# M623E.net
KiCad netlist of a schematic drawn in EAGLE
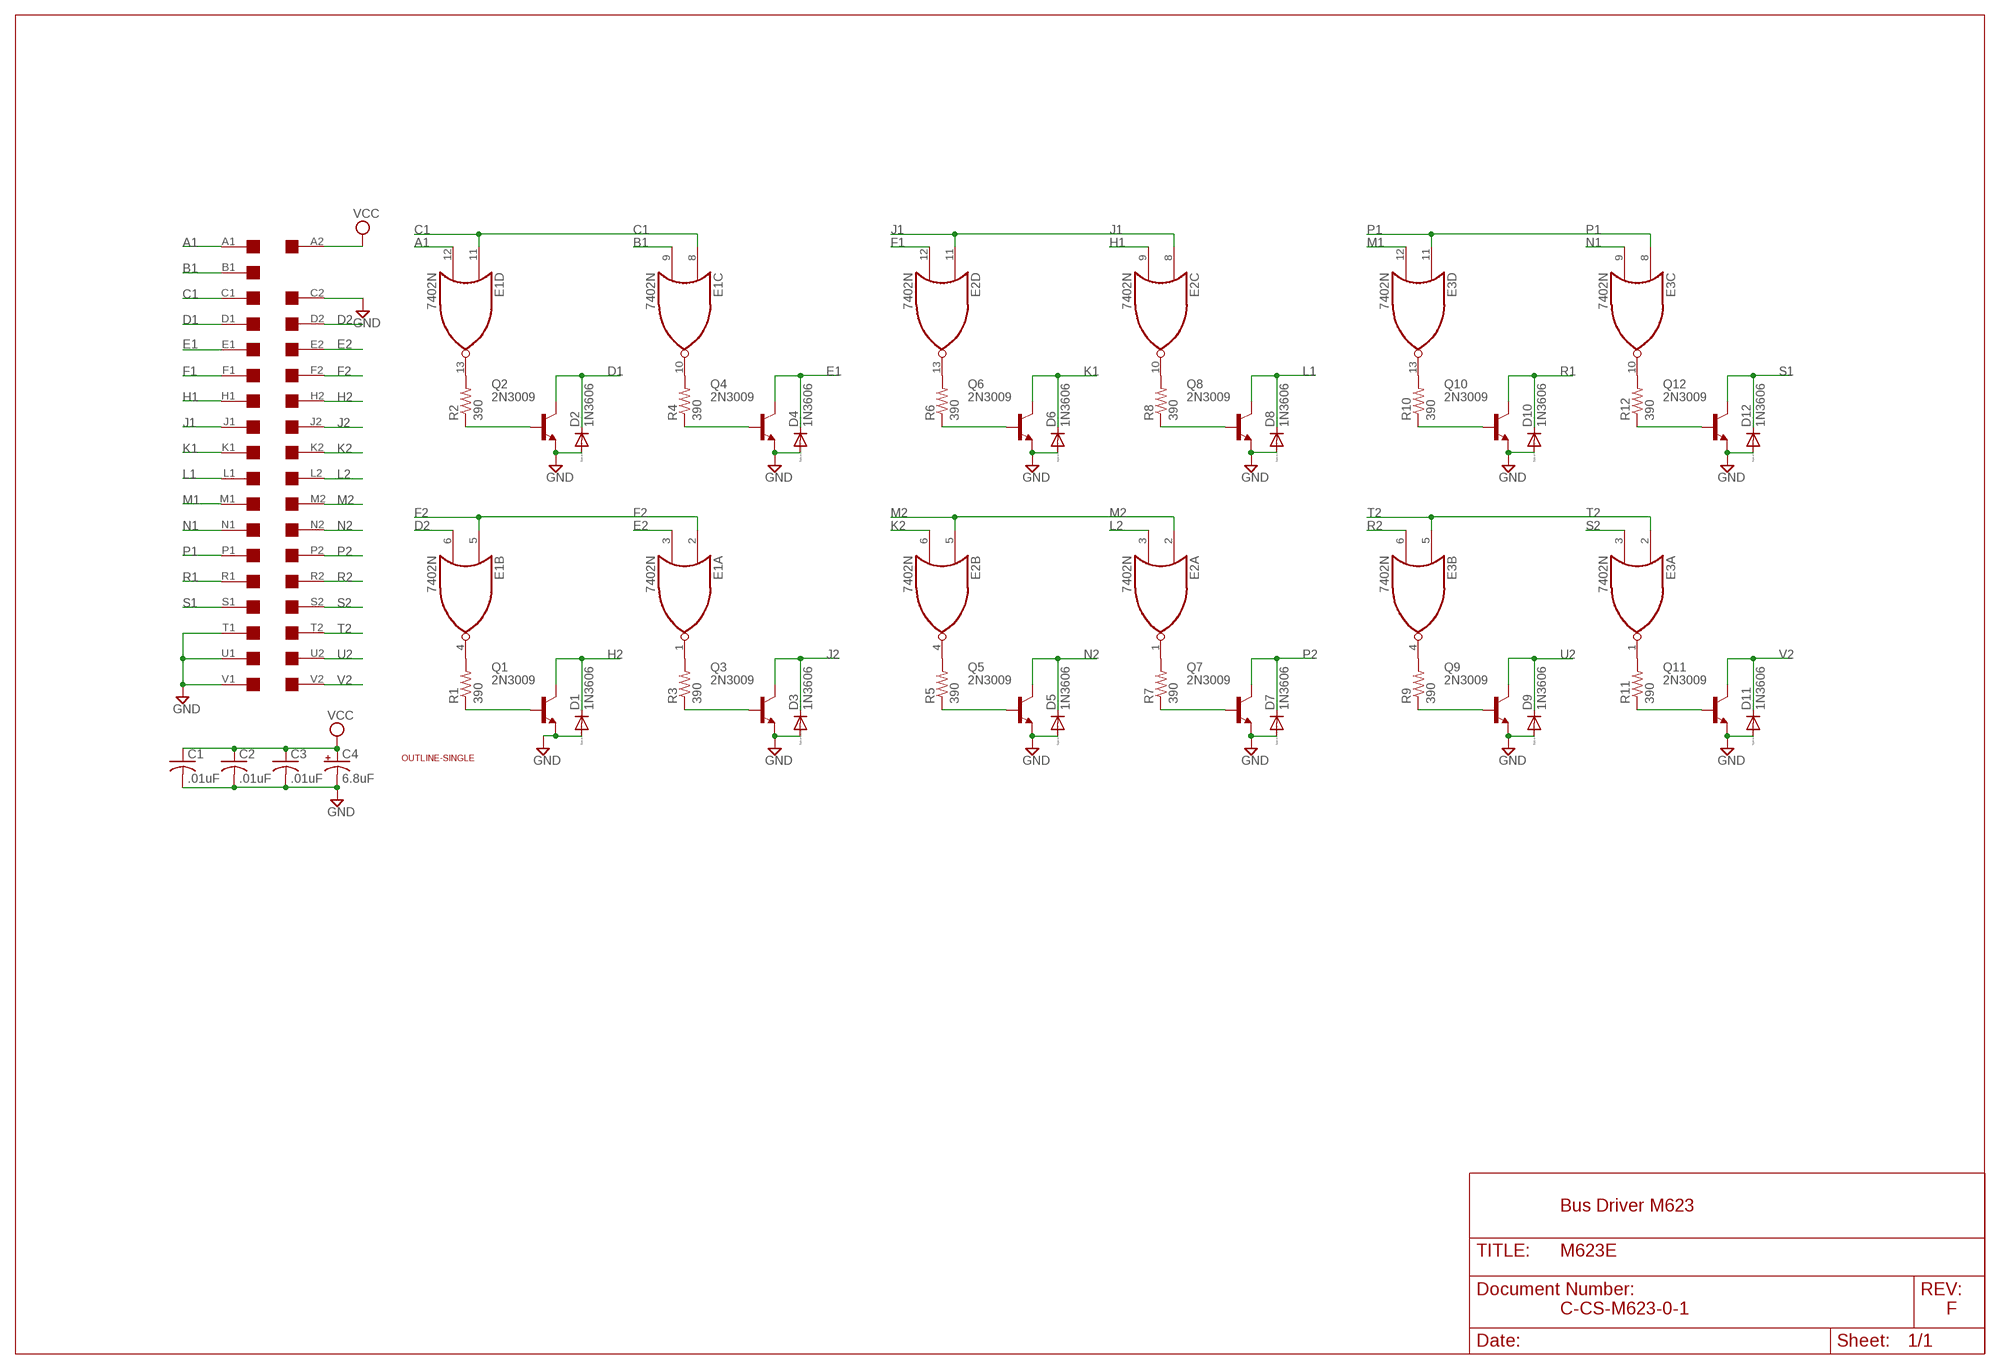
[diagram p0: schematic, sheet 1]

(export (version "E")
  (design (tool "Eeschema 10.0.6"))
  (components
    (comp (ref "C1")
      (value ".01uF")
      (footprint "eagle-import:C050-025X075")
      (libsource (lib "eagle-import") (part "C-US050-025X075"))
    )
    (comp (ref "C2")
      (value ".01uF")
      (footprint "eagle-import:C050-025X075")
      (libsource (lib "eagle-import") (part "C-US050-025X075"))
    )
    (comp (ref "C3")
      (value ".01uF")
      (footprint "eagle-import:C050-025X075")
      (libsource (lib "eagle-import") (part "C-US050-025X075"))
    )
    (comp (ref "C4")
      (value "6.8uF")
      (footprint "eagle-import:E12-8")
      (libsource (lib "eagle-import") (part "CPOL-USE20-8AXIAL"))
    )
    (comp (ref "D1")
      (value "1N3606")
      (footprint "eagle-import:DO35-10")
      (libsource (lib "eagle-import") (part "1N4148DO35-10"))
    )
    (comp (ref "D2")
      (value "1N3606")
      (footprint "eagle-import:DO35-10")
      (libsource (lib "eagle-import") (part "1N4148DO35-10"))
    )
    (comp (ref "D3")
      (value "1N3606")
      (footprint "eagle-import:DO35-10")
      (libsource (lib "eagle-import") (part "1N4148DO35-10"))
    )
    (comp (ref "D4")
      (value "1N3606")
      (footprint "eagle-import:DO35-10")
      (libsource (lib "eagle-import") (part "1N4148DO35-10"))
    )
    (comp (ref "D5")
      (value "1N3606")
      (footprint "eagle-import:DO35-10")
      (libsource (lib "eagle-import") (part "1N4148DO35-10"))
    )
    (comp (ref "D6")
      (value "1N3606")
      (footprint "eagle-import:DO35-10")
      (libsource (lib "eagle-import") (part "1N4148DO35-10"))
    )
    (comp (ref "D7")
      (value "1N3606")
      (footprint "eagle-import:DO35-10")
      (libsource (lib "eagle-import") (part "1N4148DO35-10"))
    )
    (comp (ref "D8")
      (value "1N3606")
      (footprint "eagle-import:DO35-10")
      (libsource (lib "eagle-import") (part "1N4148DO35-10"))
    )
    (comp (ref "D9")
      (value "1N3606")
      (footprint "eagle-import:DO35-10")
      (libsource (lib "eagle-import") (part "1N4148DO35-10"))
    )
    (comp (ref "D10")
      (value "1N3606")
      (footprint "eagle-import:DO35-10")
      (libsource (lib "eagle-import") (part "1N4148DO35-10"))
    )
    (comp (ref "D11")
      (value "1N3606")
      (footprint "eagle-import:DO35-10")
      (libsource (lib "eagle-import") (part "1N4148DO35-10"))
    )
    (comp (ref "D12")
      (value "1N3606")
      (footprint "eagle-import:DO35-10")
      (libsource (lib "eagle-import") (part "1N4148DO35-10"))
    )
    (comp (ref "E1")
      (value "7402N")
      (footprint "eagle-import:DIL14")
      (libsource (lib "eagle-import") (part "7402N"))
    )
    (comp (ref "E2")
      (value "7402N")
      (footprint "eagle-import:DIL14")
      (libsource (lib "eagle-import") (part "7402N"))
    )
    (comp (ref "E3")
      (value "7402N")
      (footprint "eagle-import:DIL14")
      (libsource (lib "eagle-import") (part "7402N"))
    )
    (comp (ref "Q1")
      (value "2N3009")
      (footprint "eagle-import:TO39")
      (libsource (lib "eagle-import") (part "-NPN-TO39-EBC2N1613"))
    )
    (comp (ref "Q2")
      (value "2N3009")
      (footprint "eagle-import:TO39")
      (libsource (lib "eagle-import") (part "-NPN-TO39-EBC2N1613"))
    )
    (comp (ref "Q3")
      (value "2N3009")
      (footprint "eagle-import:TO39")
      (libsource (lib "eagle-import") (part "-NPN-TO39-EBC2N1613"))
    )
    (comp (ref "Q4")
      (value "2N3009")
      (footprint "eagle-import:TO39")
      (libsource (lib "eagle-import") (part "-NPN-TO39-EBC2N1613"))
    )
    (comp (ref "Q5")
      (value "2N3009")
      (footprint "eagle-import:TO39")
      (libsource (lib "eagle-import") (part "-NPN-TO39-EBC2N1613"))
    )
    (comp (ref "Q6")
      (value "2N3009")
      (footprint "eagle-import:TO39")
      (libsource (lib "eagle-import") (part "-NPN-TO39-EBC2N1613"))
    )
    (comp (ref "Q7")
      (value "2N3009")
      (footprint "eagle-import:TO39")
      (libsource (lib "eagle-import") (part "-NPN-TO39-EBC2N1613"))
    )
    (comp (ref "Q8")
      (value "2N3009")
      (footprint "eagle-import:TO39")
      (libsource (lib "eagle-import") (part "-NPN-TO39-EBC2N1613"))
    )
    (comp (ref "Q9")
      (value "2N3009")
      (footprint "eagle-import:TO39")
      (libsource (lib "eagle-import") (part "-NPN-TO39-EBC2N1613"))
    )
    (comp (ref "Q10")
      (value "2N3009")
      (footprint "eagle-import:TO39")
      (libsource (lib "eagle-import") (part "-NPN-TO39-EBC2N1613"))
    )
    (comp (ref "Q11")
      (value "2N3009")
      (footprint "eagle-import:TO39")
      (libsource (lib "eagle-import") (part "-NPN-TO39-EBC2N1613"))
    )
    (comp (ref "Q12")
      (value "2N3009")
      (footprint "eagle-import:TO39")
      (libsource (lib "eagle-import") (part "-NPN-TO39-EBC2N1613"))
    )
    (comp (ref "R1")
      (value "390")
      (footprint "eagle-import:0207_10")
      (libsource (lib "eagle-import") (part "R-US_0207/10"))
    )
    (comp (ref "R2")
      (value "390")
      (footprint "eagle-import:0207_10")
      (libsource (lib "eagle-import") (part "R-US_0207/10"))
    )
    (comp (ref "R3")
      (value "390")
      (footprint "eagle-import:0207_10")
      (libsource (lib "eagle-import") (part "R-US_0207/10"))
    )
    (comp (ref "R4")
      (value "390")
      (footprint "eagle-import:0207_10")
      (libsource (lib "eagle-import") (part "R-US_0207/10"))
    )
    (comp (ref "R5")
      (value "390")
      (footprint "eagle-import:0207_10")
      (libsource (lib "eagle-import") (part "R-US_0207/10"))
    )
    (comp (ref "R6")
      (value "390")
      (footprint "eagle-import:0207_10")
      (libsource (lib "eagle-import") (part "R-US_0207/10"))
    )
    (comp (ref "R7")
      (value "390")
      (footprint "eagle-import:0207_10")
      (libsource (lib "eagle-import") (part "R-US_0207/10"))
    )
    (comp (ref "R8")
      (value "390")
      (footprint "eagle-import:0207_10")
      (libsource (lib "eagle-import") (part "R-US_0207/10"))
    )
    (comp (ref "R9")
      (value "390")
      (footprint "eagle-import:0207_10")
      (libsource (lib "eagle-import") (part "R-US_0207/10"))
    )
    (comp (ref "R10")
      (value "390")
      (footprint "eagle-import:0207_10")
      (libsource (lib "eagle-import") (part "R-US_0207/10"))
    )
    (comp (ref "R11")
      (value "390")
      (footprint "eagle-import:0207_10")
      (libsource (lib "eagle-import") (part "R-US_0207/10"))
    )
    (comp (ref "R12")
      (value "390")
      (footprint "eagle-import:0207_10")
      (libsource (lib "eagle-import") (part "R-US_0207/10"))
    )
    (comp (ref "U$1")
      (value "OUTLINE-SINGLE")
      (footprint "eagle-import:SINGLE")
      (libsource (lib "eagle-import") (part "OUTLINE-SINGLE"))
    )
    (comp (ref "U$4")
      (value "SINGLE")
      (footprint "eagle-import:EDGE-CON2")
      (libsource (lib "eagle-import") (part "SINGLE"))
    )
  )
  (nets
    (net (code "1") (name "/A1") (class "Default")
      (node (ref "E1") (pin "12") (pinfunction "I1_12") (pintype "input"))
      (node (ref "U$4") (pin "A1") (pinfunction "1_A1") (pintype "bidirectional"))
    )
    (net (code "2") (name "/B1") (class "Default")
      (node (ref "E1") (pin "9") (pinfunction "I1_9") (pintype "input"))
      (node (ref "U$4") (pin "B1") (pinfunction "1_B1") (pintype "bidirectional"))
    )
    (net (code "3") (name "/C1") (class "Default")
      (node (ref "E1") (pin "11") (pinfunction "I0_11") (pintype "input"))
      (node (ref "E1") (pin "8") (pinfunction "I0_8") (pintype "input"))
      (node (ref "U$4") (pin "C1") (pinfunction "1_C1") (pintype "bidirectional"))
    )
    (net (code "4") (name "/D1") (class "Default")
      (node (ref "D2") (pin "C") (pinfunction "C_C") (pintype "passive"))
      (node (ref "Q2") (pin "3") (pinfunction "C_3") (pintype "passive"))
      (node (ref "U$4") (pin "D1") (pinfunction "1_D1") (pintype "bidirectional"))
    )
    (net (code "5") (name "/D2") (class "Default")
      (node (ref "E1") (pin "6") (pinfunction "I1_6") (pintype "input"))
      (node (ref "U$4") (pin "D2") (pinfunction "1_D2") (pintype "bidirectional"))
    )
    (net (code "6") (name "/E1") (class "Default")
      (node (ref "D4") (pin "C") (pinfunction "C_C") (pintype "passive"))
      (node (ref "Q4") (pin "3") (pinfunction "C_3") (pintype "passive"))
      (node (ref "U$4") (pin "E1") (pinfunction "1_E1") (pintype "bidirectional"))
    )
    (net (code "7") (name "/E2") (class "Default")
      (node (ref "E1") (pin "3") (pinfunction "I1_3") (pintype "input"))
      (node (ref "U$4") (pin "E2") (pinfunction "1_E2") (pintype "bidirectional"))
    )
    (net (code "8") (name "/F1") (class "Default")
      (node (ref "E2") (pin "12") (pinfunction "I1_12") (pintype "input"))
      (node (ref "U$4") (pin "F1") (pinfunction "1_F1") (pintype "bidirectional"))
    )
    (net (code "9") (name "/F2") (class "Default")
      (node (ref "E1") (pin "2") (pinfunction "I0_2") (pintype "input"))
      (node (ref "E1") (pin "5") (pinfunction "I0_5") (pintype "input"))
      (node (ref "U$4") (pin "F2") (pinfunction "1_F2") (pintype "bidirectional"))
    )
    (net (code "10") (name "/H1") (class "Default")
      (node (ref "E2") (pin "9") (pinfunction "I1_9") (pintype "input"))
      (node (ref "U$4") (pin "H1") (pinfunction "1_H1") (pintype "bidirectional"))
    )
    (net (code "11") (name "/H2") (class "Default")
      (node (ref "D1") (pin "C") (pinfunction "C_C") (pintype "passive"))
      (node (ref "Q1") (pin "3") (pinfunction "C_3") (pintype "passive"))
      (node (ref "U$4") (pin "H2") (pinfunction "1_H2") (pintype "bidirectional"))
    )
    (net (code "12") (name "/J1") (class "Default")
      (node (ref "E2") (pin "11") (pinfunction "I0_11") (pintype "input"))
      (node (ref "E2") (pin "8") (pinfunction "I0_8") (pintype "input"))
      (node (ref "U$4") (pin "J1") (pinfunction "1_J1") (pintype "bidirectional"))
    )
    (net (code "13") (name "/J2") (class "Default")
      (node (ref "D3") (pin "C") (pinfunction "C_C") (pintype "passive"))
      (node (ref "Q3") (pin "3") (pinfunction "C_3") (pintype "passive"))
      (node (ref "U$4") (pin "J2") (pinfunction "1_J2") (pintype "bidirectional"))
    )
    (net (code "14") (name "/K1") (class "Default")
      (node (ref "D6") (pin "C") (pinfunction "C_C") (pintype "passive"))
      (node (ref "Q6") (pin "3") (pinfunction "C_3") (pintype "passive"))
      (node (ref "U$4") (pin "K1") (pinfunction "1_K1") (pintype "bidirectional"))
    )
    (net (code "15") (name "/K2") (class "Default")
      (node (ref "E2") (pin "6") (pinfunction "I1_6") (pintype "input"))
      (node (ref "U$4") (pin "K2") (pinfunction "1_K2") (pintype "bidirectional"))
    )
    (net (code "16") (name "/L1") (class "Default")
      (node (ref "D8") (pin "C") (pinfunction "C_C") (pintype "passive"))
      (node (ref "Q8") (pin "3") (pinfunction "C_3") (pintype "passive"))
      (node (ref "U$4") (pin "L1") (pinfunction "1_L1") (pintype "bidirectional"))
    )
    (net (code "17") (name "/L2") (class "Default")
      (node (ref "E2") (pin "3") (pinfunction "I1_3") (pintype "input"))
      (node (ref "U$4") (pin "L2") (pinfunction "1_L2") (pintype "bidirectional"))
    )
    (net (code "18") (name "/M1") (class "Default")
      (node (ref "E3") (pin "12") (pinfunction "I1_12") (pintype "input"))
      (node (ref "U$4") (pin "M1") (pinfunction "1_M1") (pintype "bidirectional"))
    )
    (net (code "19") (name "/M2") (class "Default")
      (node (ref "E2") (pin "2") (pinfunction "I0_2") (pintype "input"))
      (node (ref "E2") (pin "5") (pinfunction "I0_5") (pintype "input"))
      (node (ref "U$4") (pin "M2") (pinfunction "1_M2") (pintype "bidirectional"))
    )
    (net (code "20") (name "/N1") (class "Default")
      (node (ref "E3") (pin "9") (pinfunction "I1_9") (pintype "input"))
      (node (ref "U$4") (pin "N1") (pinfunction "1_N1") (pintype "bidirectional"))
    )
    (net (code "21") (name "/N2") (class "Default")
      (node (ref "D5") (pin "C") (pinfunction "C_C") (pintype "passive"))
      (node (ref "Q5") (pin "3") (pinfunction "C_3") (pintype "passive"))
      (node (ref "U$4") (pin "N2") (pinfunction "1_N2") (pintype "bidirectional"))
    )
    (net (code "22") (name "/P1") (class "Default")
      (node (ref "E3") (pin "11") (pinfunction "I0_11") (pintype "input"))
      (node (ref "E3") (pin "8") (pinfunction "I0_8") (pintype "input"))
      (node (ref "U$4") (pin "P1") (pinfunction "1_P1") (pintype "bidirectional"))
    )
    (net (code "23") (name "/P2") (class "Default")
      (node (ref "D7") (pin "C") (pinfunction "C_C") (pintype "passive"))
      (node (ref "Q7") (pin "3") (pinfunction "C_3") (pintype "passive"))
      (node (ref "U$4") (pin "P2") (pinfunction "1_P2") (pintype "bidirectional"))
    )
    (net (code "24") (name "/R1") (class "Default")
      (node (ref "D10") (pin "C") (pinfunction "C_C") (pintype "passive"))
      (node (ref "Q10") (pin "3") (pinfunction "C_3") (pintype "passive"))
      (node (ref "U$4") (pin "R1") (pinfunction "1_R1") (pintype "bidirectional"))
    )
    (net (code "25") (name "/R2") (class "Default")
      (node (ref "E3") (pin "6") (pinfunction "I1_6") (pintype "input"))
      (node (ref "U$4") (pin "R2") (pinfunction "1_R2") (pintype "bidirectional"))
    )
    (net (code "26") (name "/S1") (class "Default")
      (node (ref "D12") (pin "C") (pinfunction "C_C") (pintype "passive"))
      (node (ref "Q12") (pin "3") (pinfunction "C_3") (pintype "passive"))
      (node (ref "U$4") (pin "S1") (pinfunction "1_S1") (pintype "bidirectional"))
    )
    (net (code "27") (name "/S2") (class "Default")
      (node (ref "E3") (pin "3") (pinfunction "I1_3") (pintype "input"))
      (node (ref "U$4") (pin "S2") (pinfunction "1_S2") (pintype "bidirectional"))
    )
    (net (code "28") (name "/T2") (class "Default")
      (node (ref "E3") (pin "2") (pinfunction "I0_2") (pintype "input"))
      (node (ref "E3") (pin "5") (pinfunction "I0_5") (pintype "input"))
      (node (ref "U$4") (pin "T2") (pinfunction "1_T2") (pintype "bidirectional"))
    )
    (net (code "29") (name "/U2") (class "Default")
      (node (ref "D9") (pin "C") (pinfunction "C_C") (pintype "passive"))
      (node (ref "Q9") (pin "3") (pinfunction "C_3") (pintype "passive"))
      (node (ref "U$4") (pin "U2") (pinfunction "1_U2") (pintype "bidirectional"))
    )
    (net (code "30") (name "/V2") (class "Default")
      (node (ref "D11") (pin "C") (pinfunction "C_C") (pintype "passive"))
      (node (ref "Q11") (pin "3") (pinfunction "C_3") (pintype "passive"))
      (node (ref "U$4") (pin "V2") (pinfunction "1_V2") (pintype "bidirectional"))
    )
    (net (code "31") (name "GND") (class "Default")
      (node (ref "C1") (pin "2") (pinfunction "2_2") (pintype "passive"))
      (node (ref "C2") (pin "2") (pinfunction "2_2") (pintype "passive"))
      (node (ref "C3") (pin "2") (pinfunction "2_2") (pintype "passive"))
      (node (ref "C4") (pin "-") (pinfunction "-_-") (pintype "passive"))
      (node (ref "D1") (pin "A") (pinfunction "A_A") (pintype "passive"))
      (node (ref "D10") (pin "A") (pinfunction "A_A") (pintype "passive"))
      (node (ref "D11") (pin "A") (pinfunction "A_A") (pintype "passive"))
      (node (ref "D12") (pin "A") (pinfunction "A_A") (pintype "passive"))
      (node (ref "D2") (pin "A") (pinfunction "A_A") (pintype "passive"))
      (node (ref "D3") (pin "A") (pinfunction "A_A") (pintype "passive"))
      (node (ref "D4") (pin "A") (pinfunction "A_A") (pintype "passive"))
      (node (ref "D5") (pin "A") (pinfunction "A_A") (pintype "passive"))
      (node (ref "D6") (pin "A") (pinfunction "A_A") (pintype "passive"))
      (node (ref "D7") (pin "A") (pinfunction "A_A") (pintype "passive"))
      (node (ref "D8") (pin "A") (pinfunction "A_A") (pintype "passive"))
      (node (ref "D9") (pin "A") (pinfunction "A_A") (pintype "passive"))
      (node (ref "Q1") (pin "1") (pinfunction "E_1") (pintype "passive"))
      (node (ref "Q10") (pin "1") (pinfunction "E_1") (pintype "passive"))
      (node (ref "Q11") (pin "1") (pinfunction "E_1") (pintype "passive"))
      (node (ref "Q12") (pin "1") (pinfunction "E_1") (pintype "passive"))
      (node (ref "Q2") (pin "1") (pinfunction "E_1") (pintype "passive"))
      (node (ref "Q3") (pin "1") (pinfunction "E_1") (pintype "passive"))
      (node (ref "Q4") (pin "1") (pinfunction "E_1") (pintype "passive"))
      (node (ref "Q5") (pin "1") (pinfunction "E_1") (pintype "passive"))
      (node (ref "Q6") (pin "1") (pinfunction "E_1") (pintype "passive"))
      (node (ref "Q7") (pin "1") (pinfunction "E_1") (pintype "passive"))
      (node (ref "Q8") (pin "1") (pinfunction "E_1") (pintype "passive"))
      (node (ref "Q9") (pin "1") (pinfunction "E_1") (pintype "passive"))
      (node (ref "U$4") (pin "C2") (pinfunction "1_C2") (pintype "bidirectional"))
      (node (ref "U$4") (pin "T1") (pinfunction "1_T1") (pintype "bidirectional"))
      (node (ref "U$4") (pin "U1") (pinfunction "1_U1") (pintype "bidirectional"))
      (node (ref "U$4") (pin "V1") (pinfunction "1_V1") (pintype "bidirectional"))
    )
    (net (code "32") (name "Net-(E1A-O)") (class "Default")
      (node (ref "E1") (pin "1") (pinfunction "O_1") (pintype "output"))
      (node (ref "R3") (pin "2") (pinfunction "2_2") (pintype "passive"))
    )
    (net (code "33") (name "Net-(E1B-O)") (class "Default")
      (node (ref "E1") (pin "4") (pinfunction "O_4") (pintype "output"))
      (node (ref "R1") (pin "2") (pinfunction "2_2") (pintype "passive"))
    )
    (net (code "34") (name "Net-(E1C-O)") (class "Default")
      (node (ref "E1") (pin "10") (pinfunction "O_10") (pintype "output"))
      (node (ref "R4") (pin "2") (pinfunction "2_2") (pintype "passive"))
    )
    (net (code "35") (name "Net-(E1D-O)") (class "Default")
      (node (ref "E1") (pin "13") (pinfunction "O_13") (pintype "output"))
      (node (ref "R2") (pin "2") (pinfunction "2_2") (pintype "passive"))
    )
    (net (code "36") (name "Net-(E2A-O)") (class "Default")
      (node (ref "E2") (pin "1") (pinfunction "O_1") (pintype "output"))
      (node (ref "R7") (pin "2") (pinfunction "2_2") (pintype "passive"))
    )
    (net (code "37") (name "Net-(E2B-O)") (class "Default")
      (node (ref "E2") (pin "4") (pinfunction "O_4") (pintype "output"))
      (node (ref "R5") (pin "2") (pinfunction "2_2") (pintype "passive"))
    )
    (net (code "38") (name "Net-(E2C-O)") (class "Default")
      (node (ref "E2") (pin "10") (pinfunction "O_10") (pintype "output"))
      (node (ref "R8") (pin "2") (pinfunction "2_2") (pintype "passive"))
    )
    (net (code "39") (name "Net-(E2D-O)") (class "Default")
      (node (ref "E2") (pin "13") (pinfunction "O_13") (pintype "output"))
      (node (ref "R6") (pin "2") (pinfunction "2_2") (pintype "passive"))
    )
    (net (code "40") (name "Net-(E3A-O)") (class "Default")
      (node (ref "E3") (pin "1") (pinfunction "O_1") (pintype "output"))
      (node (ref "R11") (pin "2") (pinfunction "2_2") (pintype "passive"))
    )
    (net (code "41") (name "Net-(E3B-O)") (class "Default")
      (node (ref "E3") (pin "4") (pinfunction "O_4") (pintype "output"))
      (node (ref "R9") (pin "2") (pinfunction "2_2") (pintype "passive"))
    )
    (net (code "42") (name "Net-(E3C-O)") (class "Default")
      (node (ref "E3") (pin "10") (pinfunction "O_10") (pintype "output"))
      (node (ref "R12") (pin "2") (pinfunction "2_2") (pintype "passive"))
    )
    (net (code "43") (name "Net-(E3D-O)") (class "Default")
      (node (ref "E3") (pin "13") (pinfunction "O_13") (pintype "output"))
      (node (ref "R10") (pin "2") (pinfunction "2_2") (pintype "passive"))
    )
    (net (code "44") (name "Net-(Q1-B)") (class "Default")
      (node (ref "Q1") (pin "2") (pinfunction "B_2") (pintype "passive"))
      (node (ref "R1") (pin "1") (pinfunction "1_1") (pintype "passive"))
    )
    (net (code "45") (name "Net-(Q2-B)") (class "Default")
      (node (ref "Q2") (pin "2") (pinfunction "B_2") (pintype "passive"))
      (node (ref "R2") (pin "1") (pinfunction "1_1") (pintype "passive"))
    )
    (net (code "46") (name "Net-(Q3-B)") (class "Default")
      (node (ref "Q3") (pin "2") (pinfunction "B_2") (pintype "passive"))
      (node (ref "R3") (pin "1") (pinfunction "1_1") (pintype "passive"))
    )
    (net (code "47") (name "Net-(Q4-B)") (class "Default")
      (node (ref "Q4") (pin "2") (pinfunction "B_2") (pintype "passive"))
      (node (ref "R4") (pin "1") (pinfunction "1_1") (pintype "passive"))
    )
    (net (code "48") (name "Net-(Q5-B)") (class "Default")
      (node (ref "Q5") (pin "2") (pinfunction "B_2") (pintype "passive"))
      (node (ref "R5") (pin "1") (pinfunction "1_1") (pintype "passive"))
    )
    (net (code "49") (name "Net-(Q6-B)") (class "Default")
      (node (ref "Q6") (pin "2") (pinfunction "B_2") (pintype "passive"))
      (node (ref "R6") (pin "1") (pinfunction "1_1") (pintype "passive"))
    )
    (net (code "50") (name "Net-(Q7-B)") (class "Default")
      (node (ref "Q7") (pin "2") (pinfunction "B_2") (pintype "passive"))
      (node (ref "R7") (pin "1") (pinfunction "1_1") (pintype "passive"))
    )
    (net (code "51") (name "Net-(Q8-B)") (class "Default")
      (node (ref "Q8") (pin "2") (pinfunction "B_2") (pintype "passive"))
      (node (ref "R8") (pin "1") (pinfunction "1_1") (pintype "passive"))
    )
    (net (code "52") (name "Net-(Q9-B)") (class "Default")
      (node (ref "Q9") (pin "2") (pinfunction "B_2") (pintype "passive"))
      (node (ref "R9") (pin "1") (pinfunction "1_1") (pintype "passive"))
    )
    (net (code "53") (name "Net-(Q10-B)") (class "Default")
      (node (ref "Q10") (pin "2") (pinfunction "B_2") (pintype "passive"))
      (node (ref "R10") (pin "1") (pinfunction "1_1") (pintype "passive"))
    )
    (net (code "54") (name "Net-(Q11-B)") (class "Default")
      (node (ref "Q11") (pin "2") (pinfunction "B_2") (pintype "passive"))
      (node (ref "R11") (pin "1") (pinfunction "1_1") (pintype "passive"))
    )
    (net (code "55") (name "Net-(Q12-B)") (class "Default")
      (node (ref "Q12") (pin "2") (pinfunction "B_2") (pintype "passive"))
      (node (ref "R12") (pin "1") (pinfunction "1_1") (pintype "passive"))
    )
    (net (code "56") (name "VCC") (class "Default")
      (node (ref "C1") (pin "1") (pinfunction "1_1") (pintype "passive"))
      (node (ref "C2") (pin "1") (pinfunction "1_1") (pintype "passive"))
      (node (ref "C3") (pin "1") (pinfunction "1_1") (pintype "passive"))
      (node (ref "C4") (pin "+") (pinfunction "+_+") (pintype "passive"))
      (node (ref "U$4") (pin "A2") (pinfunction "1_A2") (pintype "bidirectional"))
    )
  )
)
